# Power_Main_Regulators.net
KiCad netlist of a schematic drawn in Altium Designer
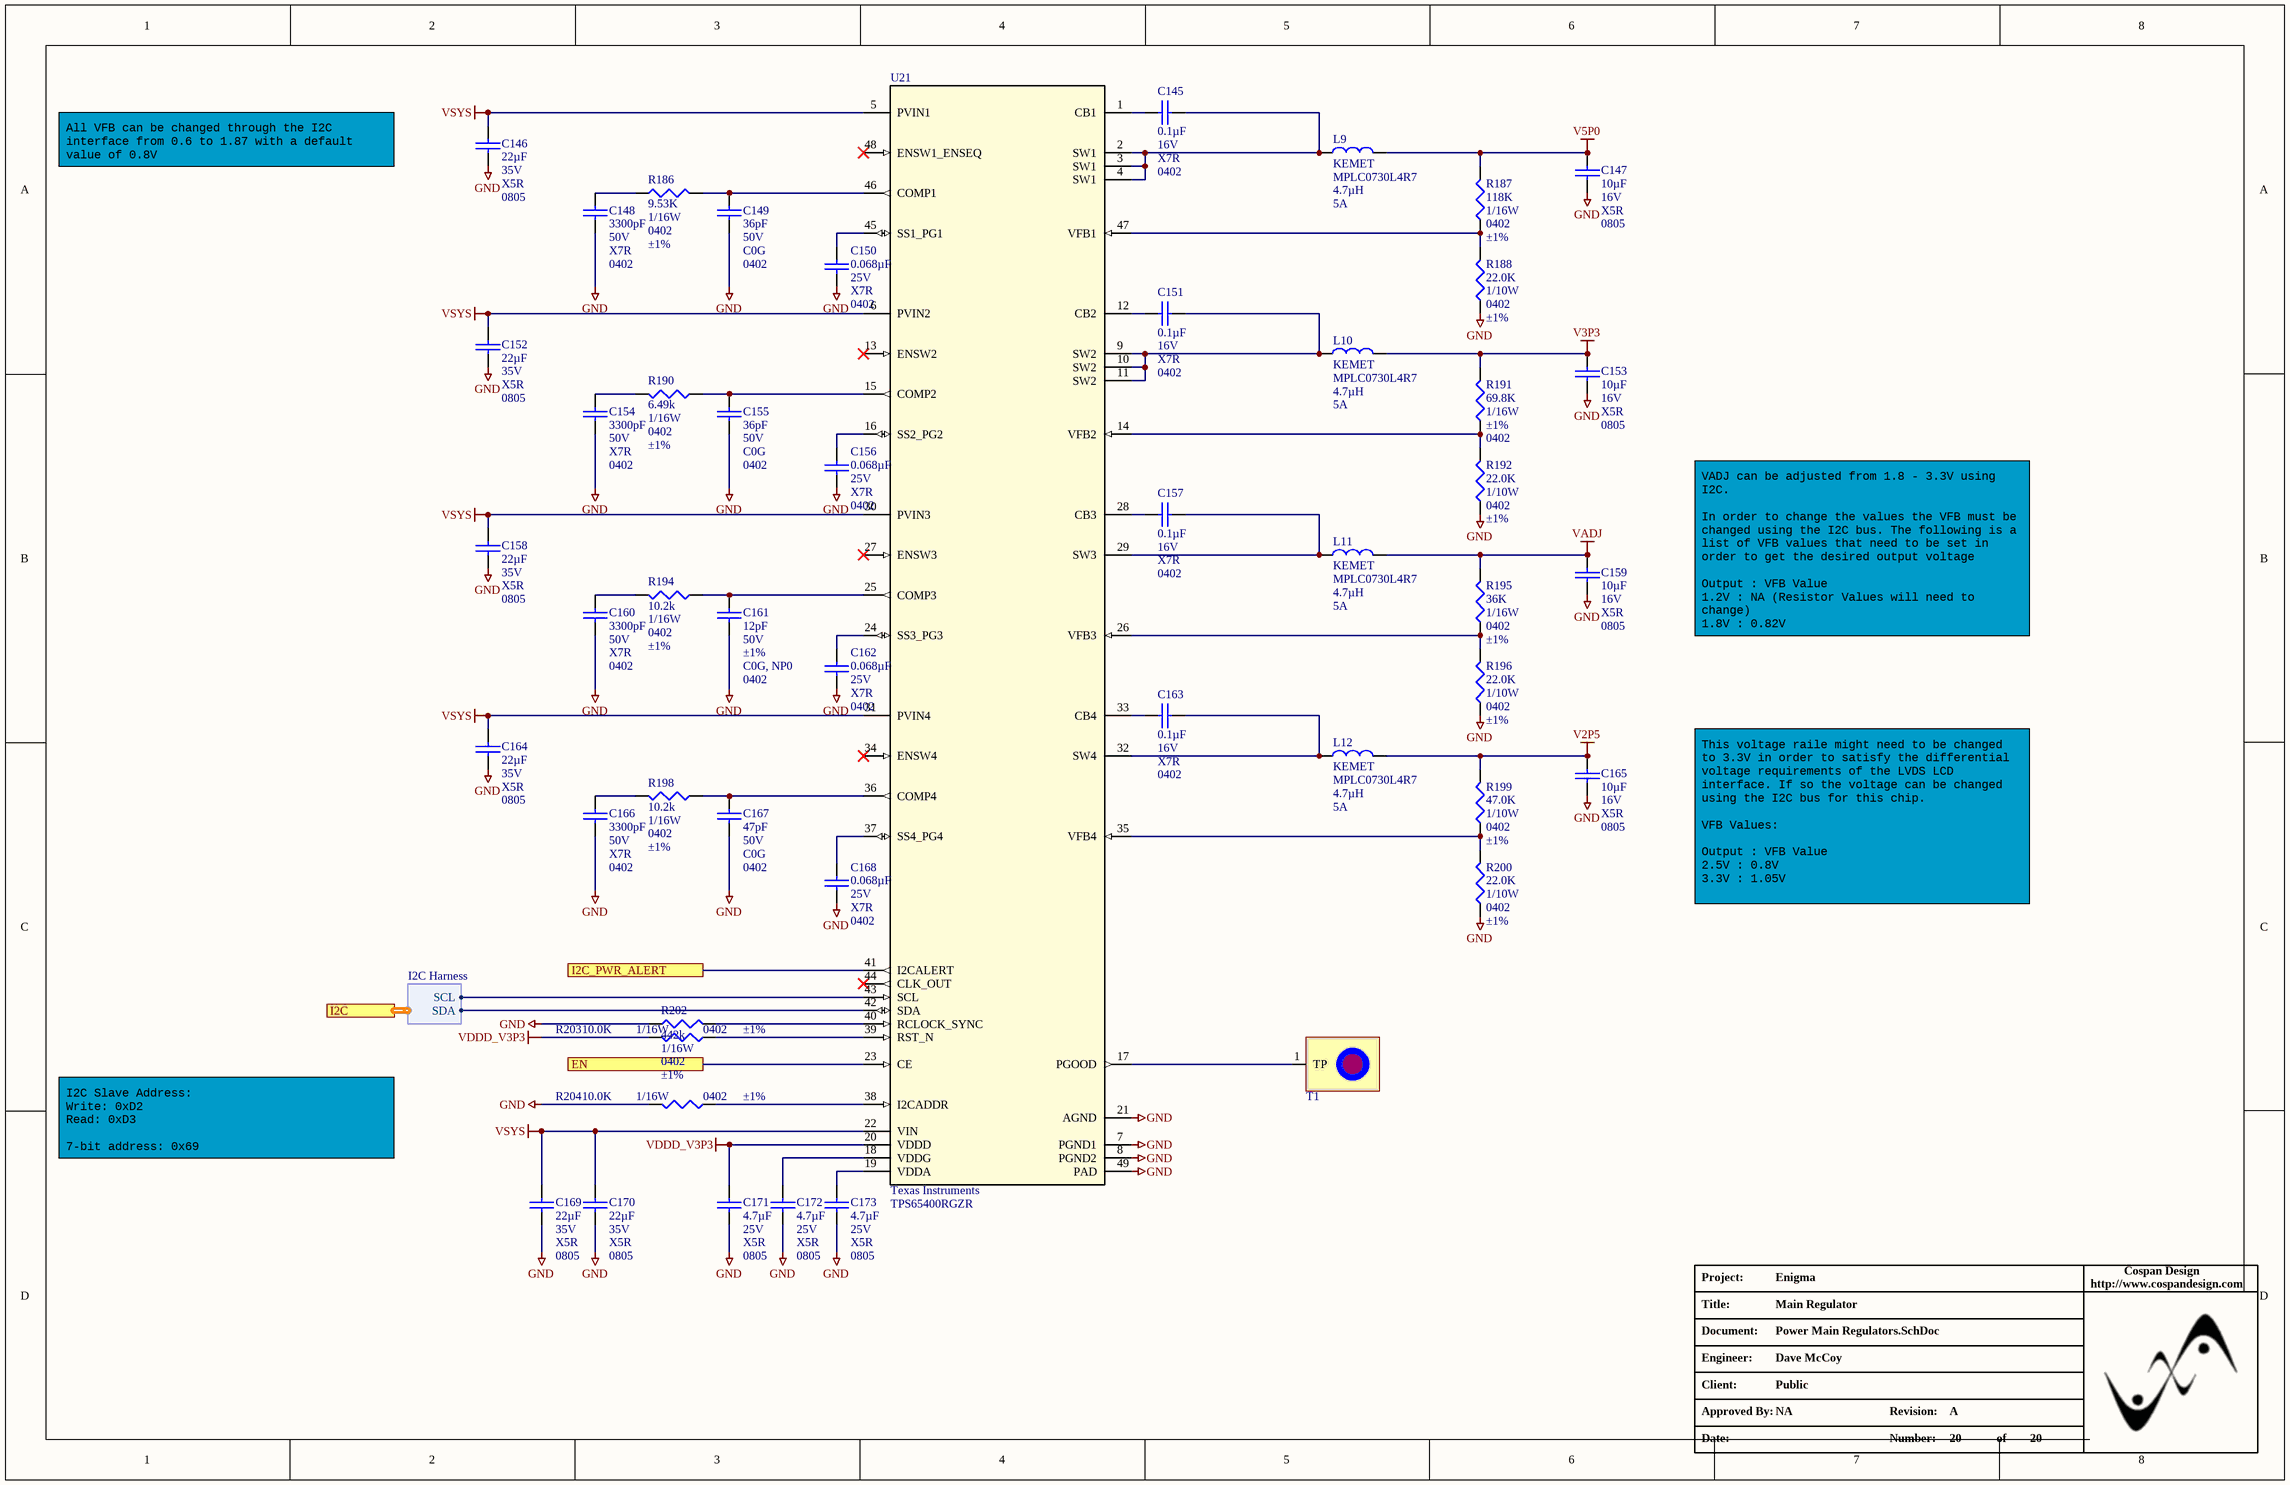
[diagram p0: Power Main Regulators.SchDoc]

(export (version "E")
  (design (tool "Eeschema 10.0.6"))
  (components
    (comp (ref "C145")
      (value "0.1uF")
      (footprint "C_0402")
      (description "CAP CER .10UF 16V X7R 0402")
      (fields
        (field (name "MANUFACTURER") "Murata Electronics North America")
        (field (name "MANUFACTURER PART NUMBER") "GRM155R71C104KA88J")
        (field (name "CAPACITANCE") "0.1µF")
        (field (name "VOLTAGE - RATED") "16V")
        (field (name "TEMPERATURE COEFFICIENT") "X7R")
        (field (name "PACKAGE / CASE") "0402")
      )
      (libsource (lib "Main LibraryX") (part "C_0402_0.1UF_16V"))
    )
    (comp (ref "C146")
      (value "C_0805_22µF_35V")
      (footprint "C_ERA-0805")
      (description "CAP CER 22UF 35V X5R 0805")
      (fields
        (field (name "MANUFACTURER") "TDK Corporation")
        (field (name "MANUFACTURER PART NUMBER") "C2012X5R1V226M125AC")
        (field (name "CAPACITANCE") "22µF")
        (field (name "VOLTAGE - RATED") "35V")
        (field (name "TEMPERATURE COEFFICIENT") "X5R")
        (field (name "PACKAGE / CASE") "0805")
      )
      (libsource (lib "Cospan Design") (part "C_0805_22µF_35V"))
    )
    (comp (ref "C147")
      (value "10µF")
      (footprint "C_ERA-0805")
      (description "CAP CER 10uF 16V X5R 20% 0805")
      (fields
        (field (name "MANUFACTURER") "Taiyo Yuden")
        (field (name "MANUFACTURER PART NUMBER") "EMK212BJ106KG-T")
        (field (name "CAPACITANCE") "10µF")
        (field (name "VOLTAGE - RATED") "16V")
        (field (name "TEMPERATURE COEFFICIENT") "X5R")
        (field (name "PACKAGE / CASE") "0805")
      )
      (libsource (lib "Main LibraryX") (part "C_0805_10UF_16V"))
    )
    (comp (ref "C148")
      (value "C_0402_3.3nF_50V")
      (footprint "C_ERA-0402")
      (fields
        (field (name "MANUFACTURER") "Murata Electronics North America")
        (field (name "MANUFACTURER PART NUMBER") "GRM155R71H332KA01D")
        (field (name "TOLERANCE") "±10%")
        (field (name "CAPACITANCE") "3300pF")
        (field (name "VOLTAGE - RATED") "50V")
        (field (name "TEMPERATURE COEFFICIENT") "X7R")
        (field (name "PACKAGE / CASE") "0402")
      )
      (libsource (lib "Main LibraryX") (part "C_0402_3.3nF_50V"))
    )
    (comp (ref "C149")
      (value "C_0402_36pF")
      (footprint "C_0402")
      (description "CAP CER 36PF 50V NP0 0402")
      (fields
        (field (name "MANUFACTURER") "Samsung Electro-Mechanics America, Inc.")
        (field (name "MANUFACTURER PART NUMBER") "CL05C360JB5NNNC")
        (field (name "CAPACITANCE") "36pF")
        (field (name "VOLTAGE - RATED") "50V")
        (field (name "TEMPERATURE COEFFICIENT") "C0G")
        (field (name "PACKAGE / CASE") "0402")
      )
      (libsource (lib "Cospan Design") (part "C_0402_36pF"))
    )
    (comp (ref "C150")
      (value "C_0402_68nF")
      (footprint "C_0402")
      (description "CAP CER 0.068UF 25V X7R 0402")
      (fields
        (field (name "MANUFACTURER") "Murata Electronics North America")
        (field (name "MANUFACTURER PART NUMBER") "GRM155R71E683KE14D")
        (field (name "CAPACITANCE") "0.068µF")
        (field (name "VOLTAGE - RATED") "25V")
        (field (name "TEMPERATURE COEFFICIENT") "X7R")
        (field (name "PACKAGE / CASE") "0402")
      )
      (libsource (lib "Cospan Design") (part "C_0402_68nF"))
    )
    (comp (ref "C151")
      (value "0.1uF")
      (footprint "C_0402")
      (description "CAP CER .10UF 16V X7R 0402")
      (fields
        (field (name "MANUFACTURER") "Murata Electronics North America")
        (field (name "MANUFACTURER PART NUMBER") "GRM155R71C104KA88J")
        (field (name "CAPACITANCE") "0.1µF")
        (field (name "VOLTAGE - RATED") "16V")
        (field (name "TEMPERATURE COEFFICIENT") "X7R")
        (field (name "PACKAGE / CASE") "0402")
      )
      (libsource (lib "Main LibraryX") (part "C_0402_0.1UF_16V"))
    )
    (comp (ref "C152")
      (value "C_0805_22µF_35V")
      (footprint "C_ERA-0805")
      (description "CAP CER 22UF 35V X5R 0805")
      (fields
        (field (name "MANUFACTURER") "TDK Corporation")
        (field (name "MANUFACTURER PART NUMBER") "C2012X5R1V226M125AC")
        (field (name "CAPACITANCE") "22µF")
        (field (name "VOLTAGE - RATED") "35V")
        (field (name "TEMPERATURE COEFFICIENT") "X5R")
        (field (name "PACKAGE / CASE") "0805")
      )
      (libsource (lib "Cospan Design") (part "C_0805_22µF_35V"))
    )
    (comp (ref "C153")
      (value "10µF")
      (footprint "C_ERA-0805")
      (description "CAP CER 10uF 16V X5R 20% 0805")
      (fields
        (field (name "MANUFACTURER") "Taiyo Yuden")
        (field (name "MANUFACTURER PART NUMBER") "EMK212BJ106KG-T")
        (field (name "CAPACITANCE") "10µF")
        (field (name "VOLTAGE - RATED") "16V")
        (field (name "TEMPERATURE COEFFICIENT") "X5R")
        (field (name "PACKAGE / CASE") "0805")
      )
      (libsource (lib "Main LibraryX") (part "C_0805_10UF_16V"))
    )
    (comp (ref "C154")
      (value "C_0402_3.3nF_50V")
      (footprint "C_ERA-0402")
      (fields
        (field (name "MANUFACTURER") "Murata Electronics North America")
        (field (name "MANUFACTURER PART NUMBER") "GRM155R71H332KA01D")
        (field (name "TOLERANCE") "±10%")
        (field (name "CAPACITANCE") "3300pF")
        (field (name "VOLTAGE - RATED") "50V")
        (field (name "TEMPERATURE COEFFICIENT") "X7R")
        (field (name "PACKAGE / CASE") "0402")
      )
      (libsource (lib "Main LibraryX") (part "C_0402_3.3nF_50V"))
    )
    (comp (ref "C155")
      (value "C_0402_36pF")
      (footprint "C_0402")
      (description "CAP CER 36PF 50V NP0 0402")
      (fields
        (field (name "MANUFACTURER") "Samsung Electro-Mechanics America, Inc.")
        (field (name "MANUFACTURER PART NUMBER") "CL05C360JB5NNNC")
        (field (name "CAPACITANCE") "36pF")
        (field (name "VOLTAGE - RATED") "50V")
        (field (name "TEMPERATURE COEFFICIENT") "C0G")
        (field (name "PACKAGE / CASE") "0402")
      )
      (libsource (lib "Cospan Design") (part "C_0402_36pF"))
    )
    (comp (ref "C156")
      (value "C_0402_68nF")
      (footprint "C_0402")
      (description "CAP CER 0.068UF 25V X7R 0402")
      (fields
        (field (name "MANUFACTURER") "Murata Electronics North America")
        (field (name "MANUFACTURER PART NUMBER") "GRM155R71E683KE14D")
        (field (name "CAPACITANCE") "0.068µF")
        (field (name "VOLTAGE - RATED") "25V")
        (field (name "TEMPERATURE COEFFICIENT") "X7R")
        (field (name "PACKAGE / CASE") "0402")
      )
      (libsource (lib "Cospan Design") (part "C_0402_68nF"))
    )
    (comp (ref "C157")
      (value "0.1uF")
      (footprint "C_0402")
      (description "CAP CER .10UF 16V X7R 0402")
      (fields
        (field (name "MANUFACTURER") "Murata Electronics North America")
        (field (name "MANUFACTURER PART NUMBER") "GRM155R71C104KA88J")
        (field (name "CAPACITANCE") "0.1µF")
        (field (name "VOLTAGE - RATED") "16V")
        (field (name "TEMPERATURE COEFFICIENT") "X7R")
        (field (name "PACKAGE / CASE") "0402")
      )
      (libsource (lib "Main LibraryX") (part "C_0402_0.1UF_16V"))
    )
    (comp (ref "C158")
      (value "C_0805_22µF_35V")
      (footprint "C_ERA-0805")
      (description "CAP CER 22UF 35V X5R 0805")
      (fields
        (field (name "MANUFACTURER") "TDK Corporation")
        (field (name "MANUFACTURER PART NUMBER") "C2012X5R1V226M125AC")
        (field (name "CAPACITANCE") "22µF")
        (field (name "VOLTAGE - RATED") "35V")
        (field (name "TEMPERATURE COEFFICIENT") "X5R")
        (field (name "PACKAGE / CASE") "0805")
      )
      (libsource (lib "Cospan Design") (part "C_0805_22µF_35V"))
    )
    (comp (ref "C159")
      (value "10µF")
      (footprint "C_ERA-0805")
      (description "CAP CER 10uF 16V X5R 20% 0805")
      (fields
        (field (name "MANUFACTURER") "Taiyo Yuden")
        (field (name "MANUFACTURER PART NUMBER") "EMK212BJ106KG-T")
        (field (name "CAPACITANCE") "10µF")
        (field (name "VOLTAGE - RATED") "16V")
        (field (name "TEMPERATURE COEFFICIENT") "X5R")
        (field (name "PACKAGE / CASE") "0805")
      )
      (libsource (lib "Main LibraryX") (part "C_0805_10UF_16V"))
    )
    (comp (ref "C160")
      (value "C_0402_3.3nF_50V")
      (footprint "C_ERA-0402")
      (fields
        (field (name "MANUFACTURER") "Murata Electronics North America")
        (field (name "MANUFACTURER PART NUMBER") "GRM155R71H332KA01D")
        (field (name "TOLERANCE") "±10%")
        (field (name "CAPACITANCE") "3300pF")
        (field (name "VOLTAGE - RATED") "50V")
        (field (name "TEMPERATURE COEFFICIENT") "X7R")
        (field (name "PACKAGE / CASE") "0402")
      )
      (libsource (lib "Main LibraryX") (part "C_0402_3.3nF_50V"))
    )
    (comp (ref "C161")
      (value "12pF")
      (footprint "C_ERA-0402")
      (description "CAP CER 12PF 50V 5% C0G 0402")
      (fields
        (field (name "MANUFACTURER") "Murata Electronics North America")
        (field (name "MANUFACTURER PART NUMBER") "GRM1555C1H120FA01D")
        (field (name "CAPACITANCE") "12pF")
        (field (name "VOLTAGE - RATED") "50V")
        (field (name "TOLERANCE") "±1%")
        (field (name "TEMPERATURE COEFFICIENT") "C0G, NP0")
        (field (name "PACKAGE / CASE") "0402")
      )
      (libsource (lib "Main LibraryX") (part "C_0402_12PF_50V"))
    )
    (comp (ref "C162")
      (value "C_0402_68nF")
      (footprint "C_0402")
      (description "CAP CER 0.068UF 25V X7R 0402")
      (fields
        (field (name "MANUFACTURER") "Murata Electronics North America")
        (field (name "MANUFACTURER PART NUMBER") "GRM155R71E683KE14D")
        (field (name "CAPACITANCE") "0.068µF")
        (field (name "VOLTAGE - RATED") "25V")
        (field (name "TEMPERATURE COEFFICIENT") "X7R")
        (field (name "PACKAGE / CASE") "0402")
      )
      (libsource (lib "Cospan Design") (part "C_0402_68nF"))
    )
    (comp (ref "C163")
      (value "0.1uF")
      (footprint "C_0402")
      (description "CAP CER .10UF 16V X7R 0402")
      (fields
        (field (name "MANUFACTURER") "Murata Electronics North America")
        (field (name "MANUFACTURER PART NUMBER") "GRM155R71C104KA88J")
        (field (name "CAPACITANCE") "0.1µF")
        (field (name "VOLTAGE - RATED") "16V")
        (field (name "TEMPERATURE COEFFICIENT") "X7R")
        (field (name "PACKAGE / CASE") "0402")
      )
      (libsource (lib "Main LibraryX") (part "C_0402_0.1UF_16V"))
    )
    (comp (ref "C164")
      (value "C_0805_22µF_35V")
      (footprint "C_ERA-0805")
      (description "CAP CER 22UF 35V X5R 0805")
      (fields
        (field (name "MANUFACTURER") "TDK Corporation")
        (field (name "MANUFACTURER PART NUMBER") "C2012X5R1V226M125AC")
        (field (name "CAPACITANCE") "22µF")
        (field (name "VOLTAGE - RATED") "35V")
        (field (name "TEMPERATURE COEFFICIENT") "X5R")
        (field (name "PACKAGE / CASE") "0805")
      )
      (libsource (lib "Cospan Design") (part "C_0805_22µF_35V"))
    )
    (comp (ref "C165")
      (value "10µF")
      (footprint "C_ERA-0805")
      (description "CAP CER 10uF 16V X5R 20% 0805")
      (fields
        (field (name "MANUFACTURER") "Taiyo Yuden")
        (field (name "MANUFACTURER PART NUMBER") "EMK212BJ106KG-T")
        (field (name "CAPACITANCE") "10µF")
        (field (name "VOLTAGE - RATED") "16V")
        (field (name "TEMPERATURE COEFFICIENT") "X5R")
        (field (name "PACKAGE / CASE") "0805")
      )
      (libsource (lib "Main LibraryX") (part "C_0805_10UF_16V"))
    )
    (comp (ref "C166")
      (value "C_0402_3.3nF_50V")
      (footprint "C_ERA-0402")
      (fields
        (field (name "MANUFACTURER") "Murata Electronics North America")
        (field (name "MANUFACTURER PART NUMBER") "GRM155R71H332KA01D")
        (field (name "TOLERANCE") "±10%")
        (field (name "CAPACITANCE") "3300pF")
        (field (name "VOLTAGE - RATED") "50V")
        (field (name "TEMPERATURE COEFFICIENT") "X7R")
        (field (name "PACKAGE / CASE") "0402")
      )
      (libsource (lib "Main LibraryX") (part "C_0402_3.3nF_50V"))
    )
    (comp (ref "C167")
      (value "47pF")
      (footprint "C_0402")
      (description "CAP CER 47PF 50V 5% C0G 0402")
      (fields
        (field (name "MANUFACTURER") "Murata Electronics North America")
        (field (name "MANUFACTURER PART NUMBER") "GRM1555C1H470JA01D")
        (field (name "CAPACITANCE") "47pF")
        (field (name "VOLTAGE - RATED") "50V")
        (field (name "TEMPERATURE COEFFICIENT") "C0G")
        (field (name "PACKAGE / CASE") "0402")
      )
      (libsource (lib "Main Library") (part "C_0402_47p_50V"))
    )
    (comp (ref "C168")
      (value "C_0402_68nF")
      (footprint "C_0402")
      (description "CAP CER 0.068UF 25V X7R 0402")
      (fields
        (field (name "MANUFACTURER") "Murata Electronics North America")
        (field (name "MANUFACTURER PART NUMBER") "GRM155R71E683KE14D")
        (field (name "CAPACITANCE") "0.068µF")
        (field (name "VOLTAGE - RATED") "25V")
        (field (name "TEMPERATURE COEFFICIENT") "X7R")
        (field (name "PACKAGE / CASE") "0402")
      )
      (libsource (lib "Cospan Design") (part "C_0402_68nF"))
    )
    (comp (ref "C169")
      (value "C_0805_22µF_35V")
      (footprint "C_ERA-0805")
      (description "CAP CER 22UF 35V X5R 0805")
      (fields
        (field (name "MANUFACTURER") "TDK Corporation")
        (field (name "MANUFACTURER PART NUMBER") "C2012X5R1V226M125AC")
        (field (name "CAPACITANCE") "22µF")
        (field (name "VOLTAGE - RATED") "35V")
        (field (name "TEMPERATURE COEFFICIENT") "X5R")
        (field (name "PACKAGE / CASE") "0805")
      )
      (libsource (lib "Cospan Design") (part "C_0805_22µF_35V"))
    )
    (comp (ref "C170")
      (value "C_0805_22µF_35V")
      (footprint "C_ERA-0805")
      (description "CAP CER 22UF 35V X5R 0805")
      (fields
        (field (name "MANUFACTURER") "TDK Corporation")
        (field (name "MANUFACTURER PART NUMBER") "C2012X5R1V226M125AC")
        (field (name "CAPACITANCE") "22µF")
        (field (name "VOLTAGE - RATED") "35V")
        (field (name "TEMPERATURE COEFFICIENT") "X5R")
        (field (name "PACKAGE / CASE") "0805")
      )
      (libsource (lib "Cospan Design") (part "C_0805_22µF_35V"))
    )
    (comp (ref "C171")
      (value "4.7µF")
      (footprint "C_ERA-0805")
      (description "CAP CER 4.7UF 25V 10% X5R 0805")
      (fields
        (field (name "MANUFACTURER") "Taiyo Yuden")
        (field (name "MANUFACTURER PART NUMBER") "TMK212BJ475KG-T")
        (field (name "CAPACITANCE") "4.7µF")
        (field (name "VOLTAGE - RATED") "25V")
        (field (name "TEMPERATURE COEFFICIENT") "X5R")
        (field (name "PACKAGE / CASE") "0805")
      )
      (libsource (lib "Main Library") (part "C_0805_4.7µF_25V"))
    )
    (comp (ref "C172")
      (value "4.7µF")
      (footprint "C_ERA-0805")
      (description "CAP CER 4.7UF 25V 10% X5R 0805")
      (fields
        (field (name "MANUFACTURER") "Taiyo Yuden")
        (field (name "MANUFACTURER PART NUMBER") "TMK212BJ475KG-T")
        (field (name "CAPACITANCE") "4.7µF")
        (field (name "VOLTAGE - RATED") "25V")
        (field (name "TEMPERATURE COEFFICIENT") "X5R")
        (field (name "PACKAGE / CASE") "0805")
      )
      (libsource (lib "Main Library") (part "C_0805_4.7µF_25V"))
    )
    (comp (ref "C173")
      (value "4.7µF")
      (footprint "C_ERA-0805")
      (description "CAP CER 4.7UF 25V 10% X5R 0805")
      (fields
        (field (name "MANUFACTURER") "Taiyo Yuden")
        (field (name "MANUFACTURER PART NUMBER") "TMK212BJ475KG-T")
        (field (name "CAPACITANCE") "4.7µF")
        (field (name "VOLTAGE - RATED") "25V")
        (field (name "TEMPERATURE COEFFICIENT") "X5R")
        (field (name "PACKAGE / CASE") "0805")
      )
      (libsource (lib "Main Library") (part "C_0805_4.7µF_25V"))
    )
    (comp (ref "L9")
      (value "L_MPLC0730L4R7")
      (footprint "KEM_L9004_MPLC")
      (description "FIXED IND 4.7UH 5A 41 MOHM SMD")
      (fields
        (field (name "TOLERANCE") "±20%")
        (field (name "MANUFACTURER") "KEMET")
        (field (name "MANUFACTURER PART NUMBER") "MPLC0730L4R7")
        (field (name "INDUCTANCE") "4.7µH")
        (field (name "MAX DC CURRENT") "5A")
      )
      (libsource (lib "Cospan Design") (part "L_MPLC0730L4R7"))
    )
    (comp (ref "L10")
      (value "L_MPLC0730L4R7")
      (footprint "KEM_L9004_MPLC")
      (description "FIXED IND 4.7UH 5A 41 MOHM SMD")
      (fields
        (field (name "TOLERANCE") "±20%")
        (field (name "MANUFACTURER") "KEMET")
        (field (name "MANUFACTURER PART NUMBER") "MPLC0730L4R7")
        (field (name "INDUCTANCE") "4.7µH")
        (field (name "MAX DC CURRENT") "5A")
      )
      (libsource (lib "Cospan Design") (part "L_MPLC0730L4R7"))
    )
    (comp (ref "L11")
      (value "L_MPLC0730L4R7")
      (footprint "KEM_L9004_MPLC")
      (description "FIXED IND 4.7UH 5A 41 MOHM SMD")
      (fields
        (field (name "TOLERANCE") "±20%")
        (field (name "MANUFACTURER") "KEMET")
        (field (name "MANUFACTURER PART NUMBER") "MPLC0730L4R7")
        (field (name "INDUCTANCE") "4.7µH")
        (field (name "MAX DC CURRENT") "5A")
      )
      (libsource (lib "Cospan Design") (part "L_MPLC0730L4R7"))
    )
    (comp (ref "L12")
      (value "L_MPLC0730L4R7")
      (footprint "KEM_L9004_MPLC")
      (description "FIXED IND 4.7UH 5A 41 MOHM SMD")
      (fields
        (field (name "TOLERANCE") "±20%")
        (field (name "MANUFACTURER") "KEMET")
        (field (name "MANUFACTURER PART NUMBER") "MPLC0730L4R7")
        (field (name "INDUCTANCE") "4.7µH")
        (field (name "MAX DC CURRENT") "5A")
      )
      (libsource (lib "Cospan Design") (part "L_MPLC0730L4R7"))
    )
    (comp (ref "R186")
      (value "R_0402_9.53K")
      (footprint "R_0402")
      (description "RES SMD 9.53K OHM 1% 1/16W 0402")
      (fields
        (field (name "MANUFACTURER") "Yageo")
        (field (name "MANUFACTURER PART NUMBER") "RC0402FR-079K53L")
        (field (name "RESISTANCE IN OHMS") "9.53K")
        (field (name "POWER (WATTS)") "1/16W")
        (field (name "CASE") "0402")
        (field (name "TOLERANCE") "±1%")
      )
      (libsource (lib "Cospan Design") (part "R_0402_9.53K"))
    )
    (comp (ref "R187")
      (value "R_0402_118K")
      (footprint "R_0402")
      (description "RES SMD 118K OHM 1% 1/16W 0402")
      (fields
        (field (name "MANUFACTURER") "Stackpole Electronics Inc")
        (field (name "MANUFACTURER PART NUMBER") "RMCF0402FT118K")
        (field (name "RESISTANCE IN OHMS") "118K")
        (field (name "POWER (WATTS)") "1/16W")
        (field (name "CASE") "0402")
        (field (name "TOLERANCE") "±1%")
      )
      (libsource (lib "Cospan Design") (part "R_0402_118K"))
    )
    (comp (ref "R188")
      (value "R_0402_22.0K")
      (footprint "R_0402")
      (description "RES 22.0K OHM 1/10W 1% 0402 SMD")
      (fields
        (field (name "MANUFACTURER") "Vishay Dale")
        (field (name "MANUFACTURER PART NUMBER") "CRCW040222K0FKED")
        (field (name "RESISTANCE IN OHMS") "22.0K")
        (field (name "POWER (WATTS)") "1/10W")
        (field (name "CASE") "0402")
        (field (name "TOLERANCE") "±1%")
      )
      (libsource (lib "Main Library") (part "R_0402_22.0K"))
    )
    (comp (ref "R190")
      (value "R_0402_6.49k")
      (footprint "R_0402")
      (description "RES SMD 6.49K OHM 1% 1/16W 0402")
      (fields
        (field (name "MANUFACTURER") "Samsung Electro-Mechanics America, Inc.")
        (field (name "MANUFACTURER PART NUMBER") "RC1005F6491CS")
        (field (name "RESISTANCE IN OHMS") "6.49k")
        (field (name "POWER (WATTS)") "1/16W")
        (field (name "CASE") "0402")
        (field (name "TOLERANCE") "±1%")
      )
      (libsource (lib "Cospan Design") (part "R_0402_6.49k"))
    )
    (comp (ref "R191")
      (value "R_0402_69.8K")
      (footprint "R_0402")
      (description "RES 69.8K OHM 1/16W 1% 0402 SMD")
      (fields
        (field (name "MANUFACTURER") "Yageo")
        (field (name "MANUFACTURER PART NUMBER") "RC0402FR-0769K8L")
        (field (name "RESISTANCE IN OHMS") "69.8K")
        (field (name "POWER (WATTS)") "1/16W")
        (field (name "TOLERANCE") "±1%")
        (field (name "CASE") "0402")
      )
      (libsource (lib "Main LibraryX") (part "R_0402_69.8K"))
    )
    (comp (ref "R192")
      (value "R_0402_22.0K")
      (footprint "R_0402")
      (description "RES 22.0K OHM 1/10W 1% 0402 SMD")
      (fields
        (field (name "MANUFACTURER") "Vishay Dale")
        (field (name "MANUFACTURER PART NUMBER") "CRCW040222K0FKED")
        (field (name "RESISTANCE IN OHMS") "22.0K")
        (field (name "POWER (WATTS)") "1/10W")
        (field (name "CASE") "0402")
        (field (name "TOLERANCE") "±1%")
      )
      (libsource (lib "Main Library") (part "R_0402_22.0K"))
    )
    (comp (ref "R194")
      (value "R_0402_10.2k")
      (footprint "R_0402")
      (description "RES SMD 10.2K OHM 1% 1/16W 0402")
      (fields
        (field (name "MANUFACTURER") "Stackpole Electronics Inc.")
        (field (name "MANUFACTURER PART NUMBER") "RMCF0402FT10K2")
        (field (name "RESISTANCE IN OHMS") "10.2k")
        (field (name "POWER (WATTS)") "1/16W")
        (field (name "CASE") "0402")
        (field (name "TOLERANCE") "±1%")
      )
      (libsource (lib "Cospan Design") (part "R_0402_10.2k"))
    )
    (comp (ref "R195")
      (value "R_0402_36.0K")
      (footprint "R_0402")
      (description "RES 36.0K OHM 1/10W 1% 0402 SMD")
      (fields
        (field (name "MANUFACTURER") "Panasonic - ECG")
        (field (name "MANUFACTURER PART NUMBER") "ERJ-2RKF3602X")
        (field (name "RESISTANCE IN OHMS") "36K")
        (field (name "POWER (WATTS)") "1/16W")
        (field (name "CASE") "0402")
        (field (name "TOLERANCE") "±1%")
      )
      (libsource (lib "Main Library") (part "R_0402_36.0K"))
    )
    (comp (ref "R196")
      (value "R_0402_22.0K")
      (footprint "R_0402")
      (description "RES 22.0K OHM 1/10W 1% 0402 SMD")
      (fields
        (field (name "MANUFACTURER") "Vishay Dale")
        (field (name "MANUFACTURER PART NUMBER") "CRCW040222K0FKED")
        (field (name "RESISTANCE IN OHMS") "22.0K")
        (field (name "POWER (WATTS)") "1/10W")
        (field (name "CASE") "0402")
        (field (name "TOLERANCE") "±1%")
      )
      (libsource (lib "Main Library") (part "R_0402_22.0K"))
    )
    (comp (ref "R198")
      (value "R_0402_10.2k")
      (footprint "R_0402")
      (description "RES SMD 10.2K OHM 1% 1/16W 0402")
      (fields
        (field (name "MANUFACTURER") "Stackpole Electronics Inc.")
        (field (name "MANUFACTURER PART NUMBER") "RMCF0402FT10K2")
        (field (name "RESISTANCE IN OHMS") "10.2k")
        (field (name "POWER (WATTS)") "1/16W")
        (field (name "CASE") "0402")
        (field (name "TOLERANCE") "±1%")
      )
      (libsource (lib "Cospan Design") (part "R_0402_10.2k"))
    )
    (comp (ref "R199")
      (value "R_0402_47.0K")
      (footprint "R_0402")
      (description "RES 47.0K OHM 1/10W 1% 0402 SMD")
      (fields
        (field (name "MANUFACTURER") "Panasonic - ECG")
        (field (name "MANUFACTURER PART NUMBER") "ERJ-2RKF4702X")
        (field (name "RESISTANCE IN OHMS") "47.0K")
        (field (name "POWER (WATTS)") "1/10W")
        (field (name "CASE") "0402")
        (field (name "TOLERANCE") "±1%")
      )
      (libsource (lib "Main Library") (part "R_0402_47.0K"))
    )
    (comp (ref "R200")
      (value "R_0402_22.0K")
      (footprint "R_0402")
      (description "RES 22.0K OHM 1/10W 1% 0402 SMD")
      (fields
        (field (name "MANUFACTURER") "Vishay Dale")
        (field (name "MANUFACTURER PART NUMBER") "CRCW040222K0FKED")
        (field (name "RESISTANCE IN OHMS") "22.0K")
        (field (name "POWER (WATTS)") "1/10W")
        (field (name "CASE") "0402")
        (field (name "TOLERANCE") "±1%")
      )
      (libsource (lib "Main Library") (part "R_0402_22.0K"))
    )
    (comp (ref "R202")
      (value "R_0402_442k")
      (footprint "R_0402")
      (description "RES SMD 442K OHM 1% 1/16W 0402")
      (fields
        (field (name "MANUFACTURER") "Yageo")
        (field (name "MANUFACTURER PART NUMBER") "RC0402FR-07442KL")
        (field (name "RESISTANCE IN OHMS") "442k")
        (field (name "POWER (WATTS)") "1/16W")
        (field (name "CASE") "0402")
        (field (name "TOLERANCE") "±1%")
      )
      (libsource (lib "Cospan Design") (part "R_0402_442k"))
    )
    (comp (ref "R203")
      (value "R_0402_10.0K")
      (footprint "R_0402")
      (description "RES 10.0K OHM 1/16W 1% 0402 SMD")
      (fields
        (field (name "MANUFACTURER") "Stackpole Electronics Inc")
        (field (name "MANUFACTURER PART NUMBER") "RMCF0402FT10K0")
        (field (name "RESISTANCE IN OHMS") "10.0K")
        (field (name "POWER (WATTS)") "1/16W")
        (field (name "CASE") "0402")
        (field (name "TOLERANCE") "±1%")
      )
      (libsource (lib "Cospan Design") (part "R_0402_10.0K"))
    )
    (comp (ref "R204")
      (value "R_0402_10.0K")
      (footprint "R_0402")
      (description "RES 10.0K OHM 1/16W 1% 0402 SMD")
      (fields
        (field (name "MANUFACTURER") "Stackpole Electronics Inc")
        (field (name "MANUFACTURER PART NUMBER") "RMCF0402FT10K0")
        (field (name "RESISTANCE IN OHMS") "10.0K")
        (field (name "POWER (WATTS)") "1/16W")
        (field (name "CASE") "0402")
        (field (name "TOLERANCE") "±1%")
      )
      (libsource (lib "Cospan Design") (part "R_0402_10.0K"))
    )
    (comp (ref "T1")
      (value "TEST_POINT_SMALL")
      (footprint "TestPointSmall")
      (description "OSCILLOSCOPE TEST POINT")
      (libsource (lib "Main Library") (part "TEST_POINT_SMALL"))
    )
    (comp (ref "U21")
      (value "U_TPS65400RGZR")
      (footprint "RGZ0048B")
      (description "IC REG BUCK ADJ 4A/2A QD 48VQFN")
      (fields
        (field (name "MANUFACTURER") "Texas Instruments")
        (field (name "MANUFACTURER PART NUMBER") "TPS65400RGZR")
      )
      (libsource (lib "Cospan Design") (part "U_TPS65400RGZR"))
    )
  )
  (nets
    (net (code "3") (name "/EN") (class "Default")
      (node (ref "U21") (pin "23") (pinfunction "CE_23") (pintype "input"))
    )
    (net (code "4") (name "/I2C_PWR_ALERT") (class "Default")
      (node (ref "U21") (pin "41") (pinfunction "I2CALERT_41") (pintype "output"))
    )
    (net (code "5") (name "/SCL") (class "Default")
      (node (ref "U21") (pin "43") (pinfunction "SCL_43") (pintype "input"))
    )
    (net (code "6") (name "/SDA") (class "Default")
      (node (ref "U21") (pin "42") (pinfunction "SDA_42") (pintype "bidirectional"))
    )
    (net (code "8") (name "GND") (class "Default")
      (node (ref "C146") (pin "1") (pinfunction "1_1") (pintype "passive"))
      (node (ref "C147") (pin "1") (pinfunction "1_1") (pintype "passive"))
      (node (ref "C148") (pin "1") (pinfunction "1_1") (pintype "passive"))
      (node (ref "C149") (pin "1") (pinfunction "1_1") (pintype "passive"))
      (node (ref "C150") (pin "1") (pinfunction "1_1") (pintype "passive"))
      (node (ref "C152") (pin "1") (pinfunction "1_1") (pintype "passive"))
      (node (ref "C153") (pin "1") (pinfunction "1_1") (pintype "passive"))
      (node (ref "C154") (pin "1") (pinfunction "1_1") (pintype "passive"))
      (node (ref "C155") (pin "1") (pinfunction "1_1") (pintype "passive"))
      (node (ref "C156") (pin "1") (pinfunction "1_1") (pintype "passive"))
      (node (ref "C158") (pin "1") (pinfunction "1_1") (pintype "passive"))
      (node (ref "C159") (pin "1") (pinfunction "1_1") (pintype "passive"))
      (node (ref "C160") (pin "1") (pinfunction "1_1") (pintype "passive"))
      (node (ref "C161") (pin "1") (pinfunction "1_1") (pintype "passive"))
      (node (ref "C162") (pin "1") (pinfunction "1_1") (pintype "passive"))
      (node (ref "C164") (pin "1") (pinfunction "1_1") (pintype "passive"))
      (node (ref "C165") (pin "1") (pinfunction "1_1") (pintype "passive"))
      (node (ref "C166") (pin "1") (pinfunction "1_1") (pintype "passive"))
      (node (ref "C167") (pin "1") (pinfunction "1_1") (pintype "passive"))
      (node (ref "C168") (pin "1") (pinfunction "1_1") (pintype "passive"))
      (node (ref "C169") (pin "1") (pinfunction "1_1") (pintype "passive"))
      (node (ref "C170") (pin "1") (pinfunction "1_1") (pintype "passive"))
      (node (ref "C171") (pin "1") (pinfunction "1_1") (pintype "passive"))
      (node (ref "C172") (pin "1") (pinfunction "1_1") (pintype "passive"))
      (node (ref "C173") (pin "1") (pinfunction "1_1") (pintype "passive"))
      (node (ref "R188") (pin "2") (pinfunction "2_2") (pintype "passive"))
      (node (ref "R192") (pin "2") (pinfunction "2_2") (pintype "passive"))
      (node (ref "R196") (pin "2") (pinfunction "2_2") (pintype "passive"))
      (node (ref "R200") (pin "2") (pinfunction "2_2") (pintype "passive"))
      (node (ref "R202") (pin "2") (pinfunction "2_2") (pintype "passive"))
      (node (ref "R204") (pin "1") (pinfunction "1_1") (pintype "passive"))
      (node (ref "U21") (pin "21") (pinfunction "AGND_21") (pintype "power_in"))
      (node (ref "U21") (pin "49") (pinfunction "PAD_49") (pintype "passive"))
      (node (ref "U21") (pin "7") (pinfunction "PGND1_7") (pintype "power_in"))
      (node (ref "U21") (pin "8") (pinfunction "PGND2_8") (pintype "power_in"))
    )
    (net (code "9") (name "Net-(C145-Pad1)") (class "Default")
      (node (ref "C145") (pin "1") (pinfunction "1_1") (pintype "passive"))
      (node (ref "L9") (pin "2") (pintype "passive"))
      (node (ref "U21") (pin "2") (pinfunction "SW1_2") (pintype "power_in"))
      (node (ref "U21") (pin "3") (pinfunction "SW1_3") (pintype "power_in"))
      (node (ref "U21") (pin "4") (pinfunction "SW1_4") (pintype "power_in"))
    )
    (net (code "10") (name "Net-(C148-Pad2)") (class "Default")
      (node (ref "C148") (pin "2") (pinfunction "2_2") (pintype "passive"))
      (node (ref "R186") (pin "2") (pinfunction "2_2") (pintype "passive"))
    )
    (net (code "11") (name "Net-(C151-Pad1)") (class "Default")
      (node (ref "C151") (pin "1") (pinfunction "1_1") (pintype "passive"))
      (node (ref "L10") (pin "2") (pintype "passive"))
      (node (ref "U21") (pin "10") (pinfunction "SW2_10") (pintype "passive"))
      (node (ref "U21") (pin "11") (pinfunction "SW2_11") (pintype "power_in"))
      (node (ref "U21") (pin "9") (pinfunction "SW2_9") (pintype "power_in"))
    )
    (net (code "12") (name "Net-(C154-Pad2)") (class "Default")
      (node (ref "C154") (pin "2") (pinfunction "2_2") (pintype "passive"))
      (node (ref "R190") (pin "1") (pinfunction "1_1") (pintype "passive"))
    )
    (net (code "13") (name "Net-(C160-Pad2)") (class "Default")
      (node (ref "C160") (pin "2") (pinfunction "2_2") (pintype "passive"))
      (node (ref "R194") (pin "1") (pinfunction "1_1") (pintype "passive"))
    )
    (net (code "14") (name "Net-(C166-Pad2)") (class "Default")
      (node (ref "C166") (pin "2") (pinfunction "2_2") (pintype "passive"))
      (node (ref "R198") (pin "1") (pinfunction "1_1") (pintype "passive"))
    )
    (net (code "15") (name "Net-(T1-TP)") (class "Default")
      (node (ref "T1") (pin "1") (pinfunction "TP_1") (pintype "passive"))
      (node (ref "U21") (pin "17") (pinfunction "PGOOD_17") (pintype "output"))
    )
    (net (code "16") (name "Net-(U21-CB1)") (class "Default")
      (node (ref "C145") (pin "2") (pinfunction "2_2") (pintype "passive"))
      (node (ref "U21") (pin "1") (pinfunction "CB1_1") (pintype "power_in"))
    )
    (net (code "17") (name "Net-(U21-CB2)") (class "Default")
      (node (ref "C151") (pin "2") (pinfunction "2_2") (pintype "passive"))
      (node (ref "U21") (pin "12") (pinfunction "CB2_12") (pintype "power_in"))
    )
    (net (code "18") (name "Net-(U21-CB3)") (class "Default")
      (node (ref "C157") (pin "2") (pinfunction "2_2") (pintype "passive"))
      (node (ref "U21") (pin "28") (pinfunction "CB3_28") (pintype "power_in"))
    )
    (net (code "19") (name "Net-(U21-CB4)") (class "Default")
      (node (ref "C163") (pin "2") (pinfunction "2_2") (pintype "passive"))
      (node (ref "U21") (pin "33") (pinfunction "CB4_33") (pintype "power_in"))
    )
    (net (code "20") (name "Net-(U21-COMP1)") (class "Default")
      (node (ref "C149") (pin "2") (pinfunction "2_2") (pintype "passive"))
      (node (ref "R186") (pin "1") (pinfunction "1_1") (pintype "passive"))
      (node (ref "U21") (pin "46") (pinfunction "COMP1_46") (pintype "output"))
    )
    (net (code "21") (name "Net-(U21-COMP2)") (class "Default")
      (node (ref "C155") (pin "2") (pinfunction "2_2") (pintype "passive"))
      (node (ref "R190") (pin "2") (pinfunction "2_2") (pintype "passive"))
      (node (ref "U21") (pin "15") (pinfunction "COMP2_15") (pintype "output"))
    )
    (net (code "22") (name "Net-(U21-COMP3)") (class "Default")
      (node (ref "C161") (pin "2") (pinfunction "2_2") (pintype "passive"))
      (node (ref "R194") (pin "2") (pinfunction "2_2") (pintype "passive"))
      (node (ref "U21") (pin "25") (pinfunction "COMP3_25") (pintype "output"))
    )
    (net (code "23") (name "Net-(U21-COMP4)") (class "Default")
      (node (ref "C167") (pin "2") (pinfunction "2_2") (pintype "passive"))
      (node (ref "R198") (pin "2") (pinfunction "2_2") (pintype "passive"))
      (node (ref "U21") (pin "36") (pinfunction "COMP4_36") (pintype "output"))
    )
    (net (code "24") (name "Net-(U21-I2CADDR)") (class "Default")
      (node (ref "R204") (pin "2") (pinfunction "2_2") (pintype "passive"))
      (node (ref "U21") (pin "38") (pinfunction "I2CADDR_38") (pintype "input"))
    )
    (net (code "25") (name "Net-(U21-RCLOCK_SYNC)") (class "Default")
      (node (ref "R202") (pin "1") (pinfunction "1_1") (pintype "passive"))
      (node (ref "U21") (pin "40") (pinfunction "RCLOCK_SYNC_40") (pintype "input"))
    )
    (net (code "26") (name "Net-(U21-RST_N)") (class "Default")
      (node (ref "R203") (pin "2") (pinfunction "2_2") (pintype "passive"))
      (node (ref "U21") (pin "39") (pinfunction "RST_N_39") (pintype "input"))
    )
    (net (code "27") (name "Net-(U21-SS1_PG1)") (class "Default")
      (node (ref "C150") (pin "2") (pinfunction "2_2") (pintype "passive"))
      (node (ref "U21") (pin "45") (pinfunction "SS1_PG1_45") (pintype "bidirectional"))
    )
    (net (code "28") (name "Net-(U21-SS2_PG2)") (class "Default")
      (node (ref "C156") (pin "2") (pinfunction "2_2") (pintype "passive"))
      (node (ref "U21") (pin "16") (pinfunction "SS2_PG2_16") (pintype "bidirectional"))
    )
    (net (code "29") (name "Net-(U21-SS3_PG3)") (class "Default")
      (node (ref "C162") (pin "2") (pinfunction "2_2") (pintype "passive"))
      (node (ref "U21") (pin "24") (pinfunction "SS3_PG3_24") (pintype "bidirectional"))
    )
    (net (code "30") (name "Net-(U21-SS4_PG4)") (class "Default")
      (node (ref "C168") (pin "2") (pinfunction "2_2") (pintype "passive"))
      (node (ref "U21") (pin "37") (pinfunction "SS4_PG4_37") (pintype "bidirectional"))
    )
    (net (code "31") (name "Net-(U21-SW3)") (class "Default")
      (node (ref "C157") (pin "1") (pinfunction "1_1") (pintype "passive"))
      (node (ref "L11") (pin "2") (pintype "passive"))
      (node (ref "U21") (pin "29") (pinfunction "SW3_29") (pintype "power_in"))
    )
    (net (code "32") (name "Net-(U21-SW4)") (class "Default")
      (node (ref "C163") (pin "1") (pinfunction "1_1") (pintype "passive"))
      (node (ref "L12") (pin "2") (pintype "passive"))
      (node (ref "U21") (pin "32") (pinfunction "SW4_32") (pintype "power_in"))
    )
    (net (code "33") (name "Net-(U21-VDDA)") (class "Default")
      (node (ref "C173") (pin "2") (pinfunction "2_2") (pintype "passive"))
      (node (ref "U21") (pin "19") (pinfunction "VDDA_19") (pintype "power_in"))
    )
    (net (code "34") (name "Net-(U21-VDDG)") (class "Default")
      (node (ref "C172") (pin "2") (pinfunction "2_2") (pintype "passive"))
      (node (ref "U21") (pin "18") (pinfunction "VDDG_18") (pintype "power_in"))
    )
    (net (code "35") (name "Net-(U21-VFB1)") (class "Default")
      (node (ref "R187") (pin "2") (pinfunction "2_2") (pintype "passive"))
      (node (ref "R188") (pin "1") (pinfunction "1_1") (pintype "passive"))
      (node (ref "U21") (pin "47") (pinfunction "VFB1_47") (pintype "input"))
    )
    (net (code "36") (name "Net-(U21-VFB2)") (class "Default")
      (node (ref "R191") (pin "2") (pinfunction "2_2") (pintype "passive"))
      (node (ref "R192") (pin "1") (pinfunction "1_1") (pintype "passive"))
      (node (ref "U21") (pin "14") (pinfunction "VFB2_14") (pintype "input"))
    )
    (net (code "37") (name "Net-(U21-VFB3)") (class "Default")
      (node (ref "R195") (pin "2") (pinfunction "2_2") (pintype "passive"))
      (node (ref "R196") (pin "1") (pinfunction "1_1") (pintype "passive"))
      (node (ref "U21") (pin "26") (pinfunction "VFB3_26") (pintype "input"))
    )
    (net (code "38") (name "Net-(U21-VFB4)") (class "Default")
      (node (ref "R199") (pin "2") (pinfunction "2_2") (pintype "passive"))
      (node (ref "R200") (pin "1") (pinfunction "1_1") (pintype "passive"))
      (node (ref "U21") (pin "35") (pinfunction "VFB4_35") (pintype "input"))
    )
    (net (code "39") (name "V2P5") (class "Default")
      (node (ref "C165") (pin "2") (pinfunction "2_2") (pintype "passive"))
      (node (ref "L12") (pin "1") (pintype "passive"))
      (node (ref "R199") (pin "1") (pinfunction "1_1") (pintype "passive"))
    )
    (net (code "40") (name "V3P3") (class "Default")
      (node (ref "C153") (pin "2") (pinfunction "2_2") (pintype "passive"))
      (node (ref "L10") (pin "1") (pintype "passive"))
      (node (ref "R191") (pin "1") (pinfunction "1_1") (pintype "passive"))
    )
    (net (code "41") (name "V5P0") (class "Default")
      (node (ref "C147") (pin "2") (pinfunction "2_2") (pintype "passive"))
      (node (ref "L9") (pin "1") (pintype "passive"))
      (node (ref "R187") (pin "1") (pinfunction "1_1") (pintype "passive"))
    )
    (net (code "42") (name "VADJ") (class "Default")
      (node (ref "C159") (pin "2") (pinfunction "2_2") (pintype "passive"))
      (node (ref "L11") (pin "1") (pintype "passive"))
      (node (ref "R195") (pin "1") (pinfunction "1_1") (pintype "passive"))
    )
    (net (code "43") (name "VDDD_V3P3") (class "Default")
      (node (ref "C171") (pin "2") (pinfunction "2_2") (pintype "passive"))
      (node (ref "R203") (pin "1") (pinfunction "1_1") (pintype "passive"))
      (node (ref "U21") (pin "20") (pinfunction "VDDD_20") (pintype "power_in"))
    )
    (net (code "44") (name "VSYS") (class "Default")
      (node (ref "C146") (pin "2") (pinfunction "2_2") (pintype "passive"))
      (node (ref "C152") (pin "2") (pinfunction "2_2") (pintype "passive"))
      (node (ref "C158") (pin "2") (pinfunction "2_2") (pintype "passive"))
      (node (ref "C164") (pin "2") (pinfunction "2_2") (pintype "passive"))
      (node (ref "C169") (pin "2") (pinfunction "2_2") (pintype "passive"))
      (node (ref "C170") (pin "2") (pinfunction "2_2") (pintype "passive"))
      (node (ref "U21") (pin "22") (pinfunction "VIN_22") (pintype "power_in"))
      (node (ref "U21") (pin "30") (pinfunction "PVIN3_30") (pintype "power_in"))
      (node (ref "U21") (pin "31") (pinfunction "PVIN4_31") (pintype "power_in"))
      (node (ref "U21") (pin "5") (pinfunction "PVIN1_5") (pintype "power_in"))
      (node (ref "U21") (pin "6") (pinfunction "PVIN2_6") (pintype "power_in"))
    )
    (net (code "45") (name "unconnected-(U21-CLK_OUT-Pad44)") (class "Default")
      (node (ref "U21") (pin "44") (pinfunction "CLK_OUT_44") (pintype "output+no_connect"))
    )
    (net (code "46") (name "unconnected-(U21-ENSW1_ENSEQ-Pad48)") (class "Default")
      (node (ref "U21") (pin "48") (pinfunction "ENSW1_ENSEQ_48") (pintype "input+no_connect"))
    )
    (net (code "47") (name "unconnected-(U21-ENSW2-Pad13)") (class "Default")
      (node (ref "U21") (pin "13") (pinfunction "ENSW2_13") (pintype "input+no_connect"))
    )
    (net (code "48") (name "unconnected-(U21-ENSW3-Pad27)") (class "Default")
      (node (ref "U21") (pin "27") (pinfunction "ENSW3_27") (pintype "input+no_connect"))
    )
    (net (code "49") (name "unconnected-(U21-ENSW4-Pad34)") (class "Default")
      (node (ref "U21") (pin "34") (pinfunction "ENSW4_34") (pintype "input+no_connect"))
    )
  )
)
